# tube-core_sch-pcb.net
KiCad netlist of a schematic drawn in EAGLE
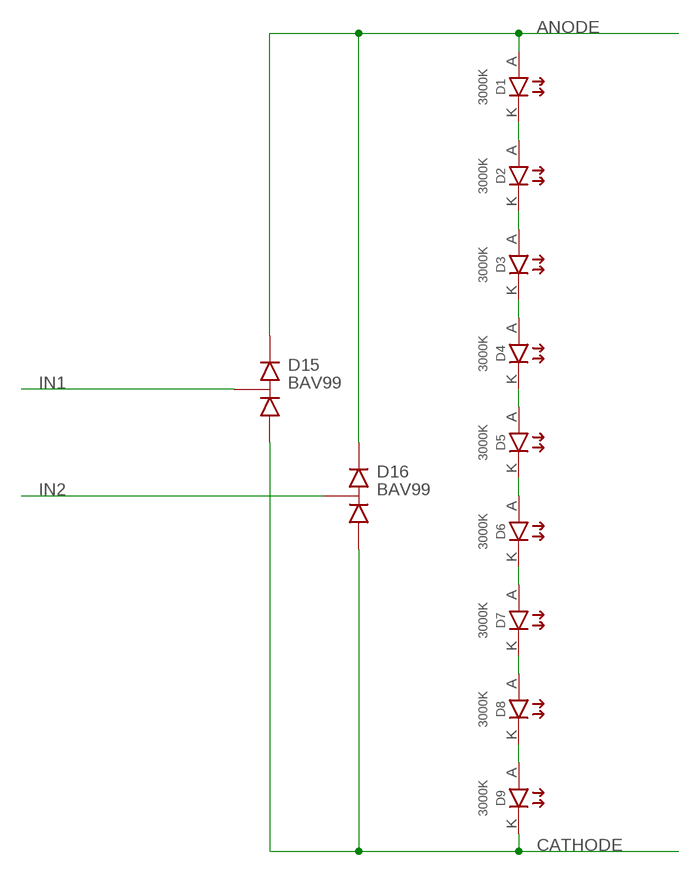
[diagram p0: schematic, sheet 1]

(export (version "E")
  (design (tool "Eeschema 10.0.6"))
  (components
    (comp (ref "D1")
      (value "3000K")
      (footprint "eagle-import:MP-1616")
      (libsource (lib "eagle-import") (part "MP-1616-1100-30-90"))
    )
    (comp (ref "D2")
      (value "3000K")
      (footprint "eagle-import:MP-1616")
      (libsource (lib "eagle-import") (part "MP-1616-1100-30-90"))
    )
    (comp (ref "D3")
      (value "3000K")
      (footprint "eagle-import:MP-1616")
      (libsource (lib "eagle-import") (part "MP-1616-1100-30-90"))
    )
    (comp (ref "D4")
      (value "3000K")
      (footprint "eagle-import:MP-1616")
      (libsource (lib "eagle-import") (part "MP-1616-1100-30-90"))
    )
    (comp (ref "D5")
      (value "3000K")
      (footprint "eagle-import:MP-1616")
      (libsource (lib "eagle-import") (part "MP-1616-1100-30-90"))
    )
    (comp (ref "D6")
      (value "3000K")
      (footprint "eagle-import:MP-1616")
      (libsource (lib "eagle-import") (part "MP-1616-1100-30-90"))
    )
    (comp (ref "D7")
      (value "3000K")
      (footprint "eagle-import:MP-1616")
      (libsource (lib "eagle-import") (part "MP-1616-1100-30-90"))
    )
    (comp (ref "D8")
      (value "3000K")
      (footprint "eagle-import:MP-1616")
      (libsource (lib "eagle-import") (part "MP-1616-1100-30-90"))
    )
    (comp (ref "D9")
      (value "3000K")
      (footprint "eagle-import:MP-1616")
      (libsource (lib "eagle-import") (part "MP-1616-1100-30-90"))
    )
    (comp (ref "D15")
      (value "BAV99")
      (footprint "eagle-import:SOT23-3")
      (libsource (lib "eagle-import") (part "BAV99"))
    )
    (comp (ref "D16")
      (value "BAV99")
      (footprint "eagle-import:SOT23-3")
      (libsource (lib "eagle-import") (part "BAV99"))
    )
  )
  (nets
    (net (code "1") (name "/ANODE") (class "Default")
      (node (ref "D1") (pin "A") (pinfunction "A_A") (pintype "bidirectional"))
      (node (ref "D15") (pin "3") (pinfunction "K_3") (pintype "bidirectional"))
      (node (ref "D16") (pin "3") (pinfunction "K_3") (pintype "bidirectional"))
    )
    (net (code "2") (name "/CATHODE") (class "Default")
      (node (ref "D15") (pin "1") (pinfunction "A_1") (pintype "bidirectional"))
      (node (ref "D16") (pin "1") (pinfunction "A_1") (pintype "bidirectional"))
      (node (ref "D9") (pin "K") (pinfunction "K_K") (pintype "bidirectional"))
    )
    (net (code "3") (name "/IN1") (class "Default")
      (node (ref "D15") (pin "2") (pinfunction "AK_2") (pintype "bidirectional"))
    )
    (net (code "4") (name "/IN2") (class "Default")
      (node (ref "D16") (pin "2") (pinfunction "AK_2") (pintype "bidirectional"))
    )
    (net (code "5") (name "Net-(D1-PadK)") (class "Default")
      (node (ref "D1") (pin "K") (pinfunction "K_K") (pintype "bidirectional"))
      (node (ref "D2") (pin "A") (pinfunction "A_A") (pintype "bidirectional"))
    )
    (net (code "6") (name "Net-(D2-PadK)") (class "Default")
      (node (ref "D2") (pin "K") (pinfunction "K_K") (pintype "bidirectional"))
      (node (ref "D3") (pin "A") (pinfunction "A_A") (pintype "bidirectional"))
    )
    (net (code "7") (name "Net-(D3-PadK)") (class "Default")
      (node (ref "D3") (pin "K") (pinfunction "K_K") (pintype "bidirectional"))
      (node (ref "D4") (pin "A") (pinfunction "A_A") (pintype "bidirectional"))
    )
    (net (code "8") (name "Net-(D4-PadK)") (class "Default")
      (node (ref "D4") (pin "K") (pinfunction "K_K") (pintype "bidirectional"))
      (node (ref "D5") (pin "A") (pinfunction "A_A") (pintype "bidirectional"))
    )
    (net (code "9") (name "Net-(D5-PadK)") (class "Default")
      (node (ref "D5") (pin "K") (pinfunction "K_K") (pintype "bidirectional"))
      (node (ref "D6") (pin "A") (pinfunction "A_A") (pintype "bidirectional"))
    )
    (net (code "10") (name "Net-(D6-PadK)") (class "Default")
      (node (ref "D6") (pin "K") (pinfunction "K_K") (pintype "bidirectional"))
      (node (ref "D7") (pin "A") (pinfunction "A_A") (pintype "bidirectional"))
    )
    (net (code "11") (name "Net-(D7-PadK)") (class "Default")
      (node (ref "D7") (pin "K") (pinfunction "K_K") (pintype "bidirectional"))
      (node (ref "D8") (pin "A") (pinfunction "A_A") (pintype "bidirectional"))
    )
    (net (code "12") (name "Net-(D8-PadK)") (class "Default")
      (node (ref "D8") (pin "K") (pinfunction "K_K") (pintype "bidirectional"))
      (node (ref "D9") (pin "A") (pinfunction "A_A") (pintype "bidirectional"))
    )
  )
)
